# Amplified_Modulator.net
KiCad netlist of a schematic drawn in Altium Designer
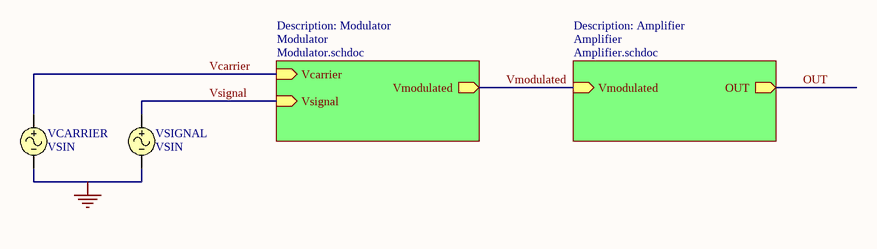
[diagram p0: Amplified Modulator.schdoc]

(export (version "E")
  (design (tool "Eeschema 10.0.6"))
  (components
    (comp (ref "VCARRIER")
      (value "VSIN")
      (description "Sinusoidal Voltage Source")
      (libsource (lib "*") (part "VSIN"))
    )
    (comp (ref "VSIGNAL")
      (value "VSIN")
      (description "Sinusoidal Voltage Source")
      (libsource (lib "*") (part "VSIN"))
    )
  )
  (nets
    (net (code "2") (name "/Vcarrier") (class "Default")
      (node (ref "VCARRIER") (pin "1") (pinfunction "1_1") (pintype "passive"))
    )
    (net (code "4") (name "/Vsignal") (class "Default")
      (node (ref "VSIGNAL") (pin "1") (pinfunction "1_1") (pintype "passive"))
    )
    (net (code "6") (name "GND") (class "Default")
      (node (ref "VCARRIER") (pin "2") (pinfunction "2_2") (pintype "passive"))
      (node (ref "VSIGNAL") (pin "2") (pinfunction "2_2") (pintype "passive"))
    )
  )
)
